# Main.net
KiCad netlist of a schematic drawn in Altium Designer
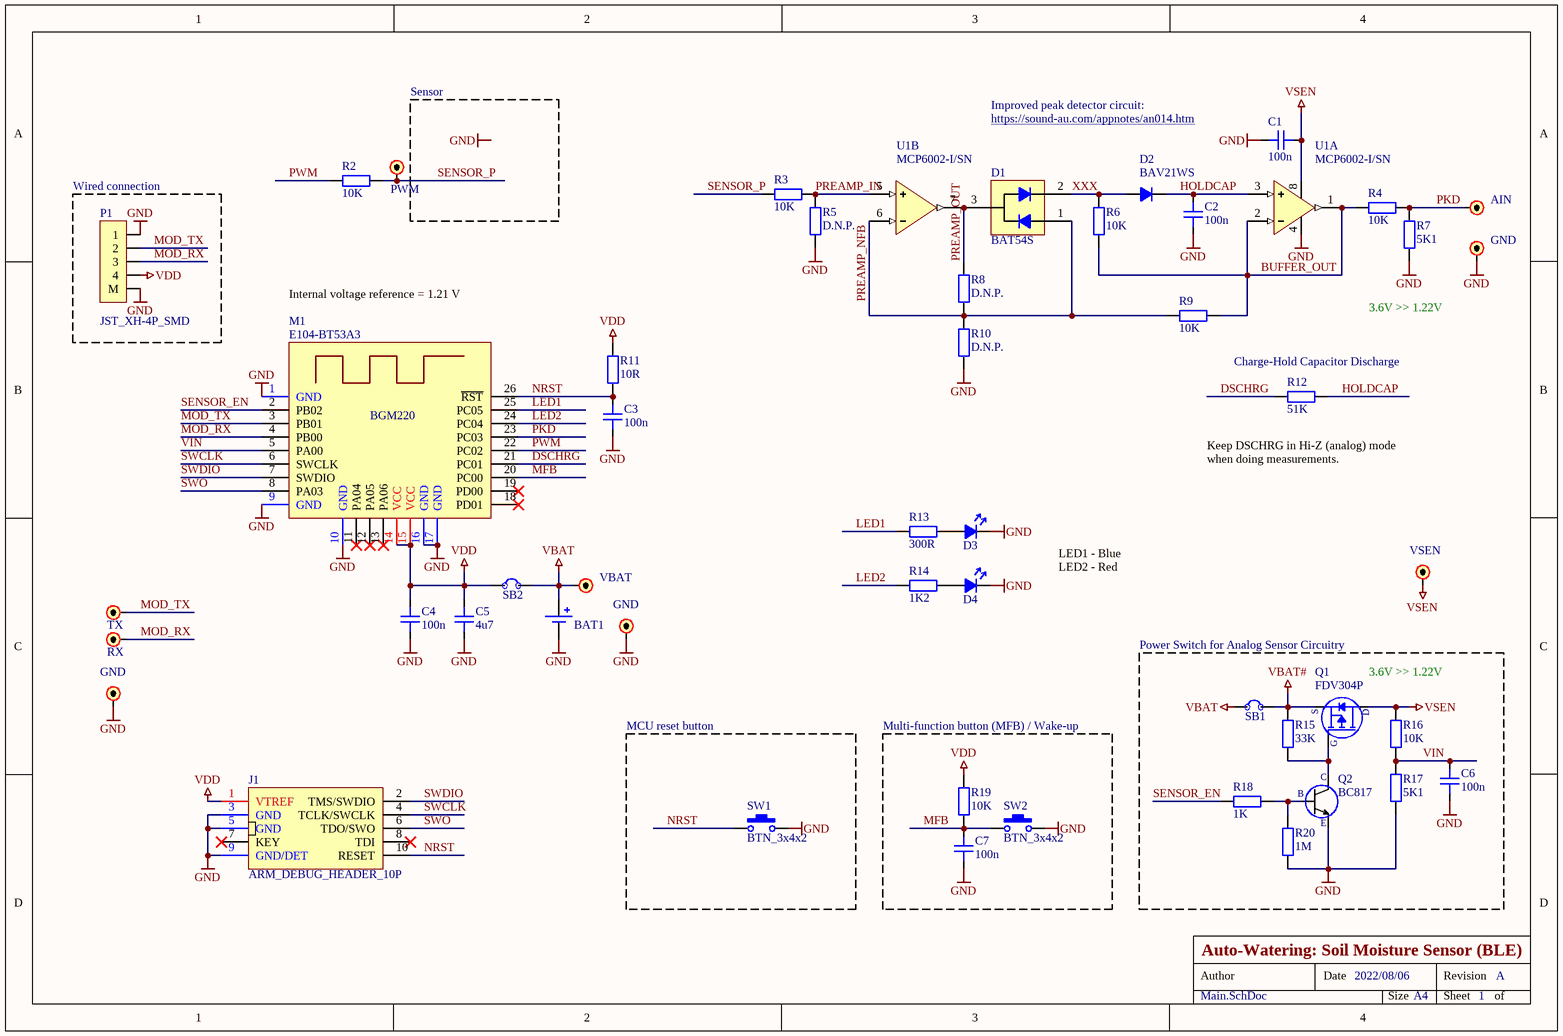
[diagram p0: Main.SchDoc]

(export (version "E")
  (design (tool "Eeschema 10.0.6"))
  (components
    (comp (ref "BAT1")
      (value "WURTH_79527141")
      (footprint "AG.Electromechanical:WURTH_79527141_NO_T-SILK")
      (description "BATT HOLDER COIN 20MM 1 CELL SMD")
      (fields
        (field (name "MANUFACTURER PART NO") "79527141")
        (field (name "MANUFACTURER") "Wurth Electronik")
      )
      (libsource (lib "AG.Holder") (part "WURTH_79527141"))
    )
    (comp (ref "C1")
      (value "100n")
      (footprint "0603C_RF_M")
      (description "Capacitor")
      (fields (field (name "TOLERANCE") "?") (field (name "MANUFACTURER") "Generic Brand"))
      (libsource (lib "AG.Generic") (part "C"))
    )
    (comp (ref "C2")
      (value "100n")
      (footprint "0603C_RF_M")
      (description "Capacitor")
      (fields (field (name "TOLERANCE") "?") (field (name "MANUFACTURER") "Generic Brand"))
      (libsource (lib "AG.Generic") (part "C"))
    )
    (comp (ref "C3")
      (value "100n")
      (footprint "0603C_RF_M")
      (description "Capacitor")
      (fields (field (name "TOLERANCE") "?") (field (name "MANUFACTURER") "Generic Brand"))
      (libsource (lib "AG.Generic") (part "C"))
    )
    (comp (ref "C4")
      (value "100n")
      (footprint "0603C_RF_M")
      (description "Capacitor")
      (fields (field (name "TOLERANCE") "?") (field (name "MANUFACTURER") "Generic Brand"))
      (libsource (lib "AG.Generic") (part "C"))
    )
    (comp (ref "C5")
      (value "4u7")
      (footprint "0603C_RF_M")
      (description "Capacitor")
      (fields (field (name "TOLERANCE") "?") (field (name "MANUFACTURER") "Generic Brand"))
      (libsource (lib "AG.Generic") (part "C"))
    )
    (comp (ref "C6")
      (value "100n")
      (footprint "0603C_RF_M")
      (description "Capacitor")
      (fields (field (name "TOLERANCE") "?") (field (name "MANUFACTURER") "Generic Brand"))
      (libsource (lib "AG.Generic") (part "C"))
    )
    (comp (ref "C7")
      (value "100n")
      (footprint "0603C_RF_M")
      (description "Capacitor")
      (fields (field (name "TOLERANCE") "?") (field (name "MANUFACTURER") "Generic Brand"))
      (libsource (lib "AG.Generic") (part "C"))
    )
    (comp (ref "D1")
      (value "BAT54S")
      (footprint "IRLML_SOT-23")
      (description "DIODE ARRAY SCHOTTKY SERIES 30V 0.2A SOT-23")
      (fields (field (name "MANUFACTURER") "Diodes Incorporated"))
      (libsource (lib "AG.Discrete") (part "BAT54S"))
    )
    (comp (ref "D2")
      (value "BAV21WS")
      (footprint "Generic:D_SOD-323")
      (description "DIODE GEN PURP 200V 200MA SOD323")
      (fields (field (name "MANUFACTURER") "Diotec"))
      (libsource (lib "Diode") (part "BAV21WS"))
    )
    (comp (ref "D3")
      (value "Unspecified")
      (footprint "0805LED_RF_M")
      (description "LED")
      (fields (field (name "MANUFACTURER") "Generic Brand"))
      (libsource (lib "AG.Generic") (part "LED"))
    )
    (comp (ref "D4")
      (value "Unspecified")
      (footprint "0805LED_RF_M")
      (description "LED")
      (fields (field (name "MANUFACTURER") "Generic Brand"))
      (libsource (lib "AG.Generic") (part "LED"))
    )
    (comp (ref "J1")
      (value "ARM_DEBUG_HEADER_10P")
      (footprint "AG.Connectors:ARM_CORTEX_DEBUG_HEADER-1.27-10P-2R_NOMASK")
      (description "ARM Cortex Debug 10-Pin Header")
      (libsource (lib "AG.Connectors") (part "ARM_DEBUG_HEADER_10P"))
    )
    (comp (ref "M1")
      (value "E104-BT53A3")
      (footprint "AG.Modules:E104-BT53A3")
      (description "RXTX MOD BLUETOOTH SOC EFR32BG22C224F512GM32")
      (libsource (lib "AG.Modules") (part "E104-BT53A3"))
    )
    (comp (ref "P1")
      (value "JST_XH-4P_SMD")
      (footprint "AG.Connectors:S4BXHSM4TBLFSN")
      (libsource (lib "AG.Connectors") (part "JST_XH-4P_SMD"))
    )
    (comp (ref "Q1")
      (value "FDV304P")
      (footprint "IRLML_SOT-23")
      (description "MOSFET P-CH 25V 460MA SOT23")
      (fields (field (name "MANUFACTURER") "ON Semiconductor (Fairchild)"))
      (libsource (lib "Transistor") (part "FDV304P"))
    )
    (comp (ref "Q2")
      (value "BC817")
      (footprint "IRLML_SOT-23")
      (description "TRANS NPN 45V 0.5A SOT23")
      (fields
        (field (name "MANUFACTURER") "Nexperia USA Inc.")
        (field (name "MANUFACTURER PART NO") "BC817-40,215")
      )
      (libsource (lib "Transistor") (part "BC817-40-215"))
    )
    (comp (ref "R2")
      (value "10K")
      (footprint "0603R_RF_M")
      (description "Resistor")
      (fields (field (name "TOLERANCE") "?") (field (name "MANUFACTURER") "Generic Brand"))
      (libsource (lib "AG.Generic") (part "R"))
    )
    (comp (ref "R3")
      (value "10K")
      (footprint "0603R_RF_M")
      (description "Resistor")
      (fields (field (name "TOLERANCE") "?") (field (name "MANUFACTURER") "Generic Brand"))
      (libsource (lib "AG.Generic") (part "R"))
    )
    (comp (ref "R4")
      (value "10K")
      (footprint "0603R_RF_M")
      (description "Resistor")
      (fields (field (name "TOLERANCE") "?") (field (name "MANUFACTURER") "Generic Brand"))
      (libsource (lib "AG.Generic") (part "R"))
    )
    (comp (ref "R5")
      (value "D.N.P.")
      (footprint "0603R_RF_M")
      (description "Resistor")
      (fields (field (name "TOLERANCE") "?") (field (name "MANUFACTURER") "Generic Brand"))
      (libsource (lib "AG.Generic") (part "R"))
    )
    (comp (ref "R6")
      (value "10K")
      (footprint "0603R_RF_M")
      (description "Resistor")
      (fields (field (name "TOLERANCE") "?") (field (name "MANUFACTURER") "Generic Brand"))
      (libsource (lib "AG.Generic") (part "R"))
    )
    (comp (ref "R7")
      (value "5K1")
      (footprint "0603R_RF_M")
      (description "Resistor")
      (fields (field (name "TOLERANCE") "?") (field (name "MANUFACTURER") "Generic Brand"))
      (libsource (lib "AG.Generic") (part "R"))
    )
    (comp (ref "R8")
      (value "D.N.P.")
      (footprint "0603R_RF_M")
      (description "Resistor")
      (fields (field (name "TOLERANCE") "?") (field (name "MANUFACTURER") "Generic Brand"))
      (libsource (lib "AG.Generic") (part "R"))
    )
    (comp (ref "R9")
      (value "10K")
      (footprint "0603R_RF_M")
      (description "Resistor")
      (fields (field (name "TOLERANCE") "?") (field (name "MANUFACTURER") "Generic Brand"))
      (libsource (lib "AG.Generic") (part "R"))
    )
    (comp (ref "R10")
      (value "D.N.P.")
      (footprint "0603R_RF_M")
      (description "Resistor")
      (fields (field (name "TOLERANCE") "?") (field (name "MANUFACTURER") "Generic Brand"))
      (libsource (lib "AG.Generic") (part "R"))
    )
    (comp (ref "R11")
      (value "10R")
      (footprint "0603R_RF_M")
      (description "Resistor")
      (fields (field (name "TOLERANCE") "?") (field (name "MANUFACTURER") "Generic Brand"))
      (libsource (lib "AG.Generic") (part "R"))
    )
    (comp (ref "R12")
      (value "51K")
      (footprint "0603R_RF_M")
      (description "Resistor")
      (fields (field (name "TOLERANCE") "?") (field (name "MANUFACTURER") "Generic Brand"))
      (libsource (lib "AG.Generic") (part "R"))
    )
    (comp (ref "R13")
      (value "300R")
      (footprint "0603R_RF_M")
      (description "Resistor")
      (fields (field (name "TOLERANCE") "?") (field (name "MANUFACTURER") "Generic Brand"))
      (libsource (lib "AG.Generic") (part "R"))
    )
    (comp (ref "R14")
      (value "1K2")
      (footprint "0603R_RF_M")
      (description "Resistor")
      (fields (field (name "TOLERANCE") "?") (field (name "MANUFACTURER") "Generic Brand"))
      (libsource (lib "AG.Generic") (part "R"))
    )
    (comp (ref "R15")
      (value "33K")
      (footprint "0603R_RF_M")
      (description "Resistor")
      (fields (field (name "TOLERANCE") "?") (field (name "MANUFACTURER") "Generic Brand"))
      (libsource (lib "AG.Generic") (part "R"))
    )
    (comp (ref "R16")
      (value "10K")
      (footprint "0603R_RF_M")
      (description "Resistor")
      (fields (field (name "TOLERANCE") "?") (field (name "MANUFACTURER") "Generic Brand"))
      (libsource (lib "AG.Generic") (part "R"))
    )
    (comp (ref "R17")
      (value "5K1")
      (footprint "0603R_RF_M")
      (description "Resistor")
      (fields (field (name "TOLERANCE") "?") (field (name "MANUFACTURER") "Generic Brand"))
      (libsource (lib "AG.Generic") (part "R"))
    )
    (comp (ref "R18")
      (value "1K")
      (footprint "0603R_RF_M")
      (description "Resistor")
      (fields (field (name "TOLERANCE") "?") (field (name "MANUFACTURER") "Generic Brand"))
      (libsource (lib "AG.Generic") (part "R"))
    )
    (comp (ref "R19")
      (value "10K")
      (footprint "0603R_RF_M")
      (description "Resistor")
      (fields (field (name "TOLERANCE") "?") (field (name "MANUFACTURER") "Generic Brand"))
      (libsource (lib "AG.Generic") (part "R"))
    )
    (comp (ref "R20")
      (value "1M")
      (footprint "0603R_RF_M")
      (description "Resistor")
      (fields (field (name "TOLERANCE") "?") (field (name "MANUFACTURER") "Generic Brand"))
      (libsource (lib "AG.Generic") (part "R"))
    )
    (comp (ref "SB1")
      (value "Solder Bridge")
      (footprint "AG.Misc:SLDR_BRDG_0603_OPEN")
      (libsource (lib "AG.Misc") (part "Solder Bridge"))
    )
    (comp (ref "SB2")
      (value "Solder Bridge")
      (footprint "AG.Misc:SLDR_BRDG_0603_OPEN")
      (libsource (lib "AG.Misc") (part "Solder Bridge"))
    )
    (comp (ref "SW1")
      (value "BTN_3x4x2")
      (footprint "AG.Electromechanical:BTN_3x4x2")
      (description "Switch Micro SMD 3x4x2 mm Unbranded")
      (libsource (lib "Button") (part "BTN_3x4x2"))
    )
    (comp (ref "SW2")
      (value "BTN_3x4x2")
      (footprint "AG.Electromechanical:BTN_3x4x2")
      (description "Switch Micro SMD 3x4x2 mm Unbranded")
      (libsource (lib "Button") (part "BTN_3x4x2"))
    )
    (comp (ref "TP1")
      (value "PWM")
      (footprint "PAD_R_1MM")
      (description "Test Point / Pad")
      (libsource (lib "AG.Misc") (part "Test Point"))
    )
    (comp (ref "TP2")
      (value "VSEN")
      (footprint "PAD_R_1MM")
      (description "Test Point / Pad")
      (libsource (lib "AG.Misc") (part "Test Point"))
    )
    (comp (ref "TP4")
      (value "AIN")
      (footprint "PAD_R_1MM")
      (description "Test Point / Pad")
      (libsource (lib "AG.Misc") (part "Test Point"))
    )
    (comp (ref "TP5")
      (value "GND")
      (footprint "PAD_R_1MM")
      (description "Test Point / Pad")
      (libsource (lib "AG.Misc") (part "Test Point"))
    )
    (comp (ref "TP6")
      (value "VBAT")
      (footprint "PAD_R_1MM")
      (description "Test Point / Pad")
      (libsource (lib "AG.Misc") (part "Test Point"))
    )
    (comp (ref "TP7")
      (value "TX")
      (footprint "PAD_R_1MM")
      (description "Test Point / Pad")
      (libsource (lib "AG.Misc") (part "Test Point"))
    )
    (comp (ref "TP8")
      (value "GND")
      (footprint "PAD_R_1MM")
      (description "Test Point / Pad")
      (libsource (lib "AG.Misc") (part "Test Point"))
    )
    (comp (ref "TP9")
      (value "RX")
      (footprint "PAD_R_1MM")
      (description "Test Point / Pad")
      (libsource (lib "AG.Misc") (part "Test Point"))
    )
    (comp (ref "TP10")
      (value "GND")
      (footprint "PAD_R_1MM")
      (description "Test Point / Pad")
      (libsource (lib "AG.Misc") (part "Test Point"))
    )
    (comp (ref "U1")
      (value "MCP6002-I/SN")
      (footprint "Generic:SOIC-8")
      (description "IC OPAMP GP 2 CIRCUIT 8SOIC")
      (libsource (lib "AG.IC") (part "MCP6002-I/SN"))
    )
  )
  (nets
    (net (code "1") (name "/BUFFER_OUT") (class "Default")
      (node (ref "R4") (pin "1") (pintype "passive"))
      (node (ref "R6") (pin "2") (pintype "passive"))
      (node (ref "R9") (pin "2") (pintype "passive"))
      (node (ref "U1") (pin "1") (pintype "output"))
      (node (ref "U1") (pin "2") (pintype "input"))
    )
    (net (code "2") (name "/DSCHRG") (class "Default")
      (node (ref "M1") (pin "21") (pinfunction "PC01_21") (pintype "passive"))
      (node (ref "R12") (pin "1") (pintype "passive"))
    )
    (net (code "3") (name "/HOLDCAP") (class "Default")
      (node (ref "C2") (pin "1") (pinfunction "1_1") (pintype "passive"))
      (node (ref "D2") (pin "C") (pinfunction "C_C") (pintype "passive"))
      (node (ref "R12") (pin "2") (pintype "passive"))
      (node (ref "U1") (pin "3") (pintype "input"))
    )
    (net (code "4") (name "/LED1") (class "Default")
      (node (ref "M1") (pin "25") (pinfunction "PC05_25") (pintype "passive"))
      (node (ref "R13") (pin "1") (pintype "passive"))
    )
    (net (code "5") (name "/LED2") (class "Default")
      (node (ref "M1") (pin "24") (pinfunction "PC04_24") (pintype "passive"))
      (node (ref "R14") (pin "1") (pintype "passive"))
    )
    (net (code "6") (name "/MFB") (class "Default")
      (node (ref "C7") (pin "2") (pinfunction "2_2") (pintype "passive"))
      (node (ref "M1") (pin "20") (pinfunction "PC00_20") (pintype "passive"))
      (node (ref "R19") (pin "1") (pintype "passive"))
      (node (ref "SW2") (pin "1") (pinfunction "1_1") (pintype "passive"))
    )
    (net (code "7") (name "/MOD_RX") (class "Default")
      (node (ref "M1") (pin "4") (pinfunction "PB00_4") (pintype "passive"))
      (node (ref "P1") (pin "3") (pinfunction "3_3") (pintype "passive"))
      (node (ref "TP9") (pin "1") (pinfunction "1_1") (pintype "passive"))
    )
    (net (code "8") (name "/MOD_TX") (class "Default")
      (node (ref "M1") (pin "3") (pinfunction "PB01_3") (pintype "passive"))
      (node (ref "P1") (pin "2") (pinfunction "2_2") (pintype "passive"))
      (node (ref "TP7") (pin "1") (pinfunction "1_1") (pintype "passive"))
    )
    (net (code "9") (name "/NRST") (class "Default")
      (node (ref "C3") (pin "2") (pinfunction "2_2") (pintype "passive"))
      (node (ref "J1") (pin "10") (pinfunction "RESET_10") (pintype "passive"))
      (node (ref "M1") (pin "26") (pinfunction "~{RST}_26") (pintype "passive"))
      (node (ref "R11") (pin "1") (pintype "passive"))
      (node (ref "SW1") (pin "1") (pinfunction "1_1") (pintype "passive"))
    )
    (net (code "10") (name "/PKD") (class "Default")
      (node (ref "M1") (pin "23") (pinfunction "PC03_23") (pintype "passive"))
      (node (ref "R4") (pin "2") (pintype "passive"))
      (node (ref "R7") (pin "2") (pintype "passive"))
      (node (ref "TP4") (pin "1") (pinfunction "1_1") (pintype "passive"))
    )
    (net (code "11") (name "/PREAMP_IN") (class "Default")
      (node (ref "R3") (pin "2") (pintype "passive"))
      (node (ref "R5") (pin "2") (pintype "passive"))
      (node (ref "U1") (pin "5") (pintype "input"))
    )
    (net (code "12") (name "/PREAMP_NFB") (class "Default")
      (node (ref "D1") (pin "1") (pinfunction "A1_1") (pintype "passive"))
      (node (ref "R10") (pin "2") (pintype "passive"))
      (node (ref "R8") (pin "1") (pintype "passive"))
      (node (ref "R9") (pin "1") (pintype "passive"))
      (node (ref "U1") (pin "6") (pintype "input"))
    )
    (net (code "13") (name "/PREAMP_OUT") (class "Default")
      (node (ref "D1") (pin "3") (pinfunction "C_3") (pintype "passive"))
      (node (ref "R8") (pin "2") (pintype "passive"))
      (node (ref "U1") (pin "7") (pintype "output"))
    )
    (net (code "14") (name "/PWM") (class "Default")
      (node (ref "M1") (pin "22") (pinfunction "PC02_22") (pintype "passive"))
      (node (ref "R2") (pin "1") (pintype "passive"))
    )
    (net (code "15") (name "/SENSOR_EN") (class "Default")
      (node (ref "M1") (pin "2") (pinfunction "PB02_2") (pintype "passive"))
      (node (ref "R18") (pin "1") (pintype "passive"))
    )
    (net (code "16") (name "/SENSOR_P") (class "Default")
      (node (ref "R2") (pin "2") (pintype "passive"))
      (node (ref "R3") (pin "1") (pintype "passive"))
      (node (ref "TP1") (pin "1") (pinfunction "1_1") (pintype "passive"))
    )
    (net (code "17") (name "/SWCLK") (class "Default")
      (node (ref "J1") (pin "4") (pinfunction "TCLK/SWCLK_4") (pintype "passive"))
      (node (ref "M1") (pin "6") (pinfunction "SWCLK_6") (pintype "passive"))
    )
    (net (code "18") (name "/SWDIO") (class "Default")
      (node (ref "J1") (pin "2") (pinfunction "TMS/SWDIO_2") (pintype "passive"))
      (node (ref "M1") (pin "7") (pinfunction "SWDIO_7") (pintype "passive"))
    )
    (net (code "19") (name "/SWO") (class "Default")
      (node (ref "J1") (pin "6") (pinfunction "TDO/SWO_6") (pintype "passive"))
      (node (ref "M1") (pin "8") (pinfunction "PA03_8") (pintype "passive"))
    )
    (net (code "20") (name "/VIN") (class "Default")
      (node (ref "C6") (pin "1") (pinfunction "1_1") (pintype "passive"))
      (node (ref "M1") (pin "5") (pinfunction "PA00_5") (pintype "passive"))
      (node (ref "R16") (pin "1") (pintype "passive"))
      (node (ref "R17") (pin "2") (pintype "passive"))
    )
    (net (code "21") (name "/XXX") (class "Default")
      (node (ref "D1") (pin "2") (pinfunction "A2_2") (pintype "passive"))
      (node (ref "D2") (pin "A") (pinfunction "A_A") (pintype "passive"))
      (node (ref "R6") (pin "1") (pintype "passive"))
    )
    (net (code "22") (name "GND") (class "Default")
      (node (ref "BAT1") (pin "N") (pinfunction "N_N") (pintype "power_in"))
      (node (ref "C1") (pin "2") (pinfunction "2_2") (pintype "passive"))
      (node (ref "C2") (pin "2") (pinfunction "2_2") (pintype "passive"))
      (node (ref "C3") (pin "1") (pinfunction "1_1") (pintype "passive"))
      (node (ref "C4") (pin "1") (pinfunction "1_1") (pintype "passive"))
      (node (ref "C5") (pin "1") (pinfunction "1_1") (pintype "passive"))
      (node (ref "C6") (pin "2") (pinfunction "2_2") (pintype "passive"))
      (node (ref "C7") (pin "1") (pinfunction "1_1") (pintype "passive"))
      (node (ref "D3") (pin "C") (pinfunction "C_C") (pintype "passive"))
      (node (ref "D4") (pin "C") (pinfunction "C_C") (pintype "passive"))
      (node (ref "J1") (pin "3") (pinfunction "GND_3") (pintype "passive"))
      (node (ref "J1") (pin "5") (pinfunction "GND_5") (pintype "passive"))
      (node (ref "J1") (pin "9") (pinfunction "GND/DET_9") (pintype "passive"))
      (node (ref "M1") (pin "1") (pinfunction "GND_1") (pintype "passive"))
      (node (ref "M1") (pin "10") (pinfunction "GND_10") (pintype "passive"))
      (node (ref "M1") (pin "16") (pinfunction "GND_16") (pintype "passive"))
      (node (ref "M1") (pin "17") (pinfunction "GND_17") (pintype "passive"))
      (node (ref "M1") (pin "9") (pinfunction "GND_9") (pintype "passive"))
      (node (ref "P1") (pin "1") (pinfunction "1_1") (pintype "passive"))
      (node (ref "P1") (pin "MNT") (pinfunction "M_MNT") (pintype "passive"))
      (node (ref "Q2") (pin "2") (pinfunction "Emmiter_2") (pintype "passive"))
      (node (ref "R10") (pin "1") (pintype "passive"))
      (node (ref "R17") (pin "1") (pintype "passive"))
      (node (ref "R20") (pin "1") (pintype "passive"))
      (node (ref "R5") (pin "1") (pintype "passive"))
      (node (ref "R7") (pin "1") (pintype "passive"))
      (node (ref "SW1") (pin "2") (pinfunction "2_2") (pintype "passive"))
      (node (ref "SW2") (pin "2") (pinfunction "2_2") (pintype "passive"))
      (node (ref "TP10") (pin "1") (pinfunction "1_1") (pintype "passive"))
      (node (ref "TP5") (pin "1") (pinfunction "1_1") (pintype "passive"))
      (node (ref "TP8") (pin "1") (pinfunction "1_1") (pintype "passive"))
      (node (ref "U1") (pin "4") (pintype "power_in"))
    )
    (net (code "23") (name "Net-(D3-PadA)") (class "Default")
      (node (ref "D3") (pin "A") (pinfunction "A_A") (pintype "passive"))
      (node (ref "R13") (pin "2") (pintype "passive"))
    )
    (net (code "24") (name "Net-(D4-PadA)") (class "Default")
      (node (ref "D4") (pin "A") (pinfunction "A_A") (pintype "passive"))
      (node (ref "R14") (pin "2") (pintype "passive"))
    )
    (net (code "25") (name "Net-(Q1-Gate)") (class "Default")
      (node (ref "Q1") (pin "1") (pinfunction "Gate_1") (pintype "passive"))
      (node (ref "Q2") (pin "3") (pinfunction "Collector_3") (pintype "passive"))
      (node (ref "R15") (pin "1") (pintype "passive"))
    )
    (net (code "26") (name "Net-(Q2-Base)") (class "Default")
      (node (ref "Q2") (pin "1") (pinfunction "Base_1") (pintype "passive"))
      (node (ref "R18") (pin "2") (pintype "passive"))
      (node (ref "R20") (pin "2") (pintype "passive"))
    )
    (net (code "27") (name "VBAT") (class "Default")
      (node (ref "BAT1") (pin "P") (pinfunction "P_P") (pintype "power_in"))
      (node (ref "SB1") (pin "1") (pinfunction "1_1") (pintype "passive"))
      (node (ref "SB2") (pin "2") (pinfunction "2_2") (pintype "passive"))
      (node (ref "TP6") (pin "1") (pinfunction "1_1") (pintype "passive"))
    )
    (net (code "28") (name "VBAT#") (class "Default")
      (node (ref "Q1") (pin "2") (pinfunction "Source_2") (pintype "passive"))
      (node (ref "R15") (pin "2") (pintype "passive"))
      (node (ref "SB1") (pin "2") (pinfunction "2_2") (pintype "passive"))
    )
    (net (code "29") (name "VDD") (class "Default")
      (node (ref "C4") (pin "2") (pinfunction "2_2") (pintype "passive"))
      (node (ref "C5") (pin "2") (pinfunction "2_2") (pintype "passive"))
      (node (ref "J1") (pin "1") (pinfunction "VTREF_1") (pintype "passive"))
      (node (ref "M1") (pin "14") (pinfunction "VCC_14") (pintype "passive"))
      (node (ref "M1") (pin "15") (pinfunction "VCC_15") (pintype "passive"))
      (node (ref "P1") (pin "4") (pinfunction "4_4") (pintype "passive"))
      (node (ref "R11") (pin "2") (pintype "passive"))
      (node (ref "R19") (pin "2") (pintype "passive"))
      (node (ref "SB2") (pin "1") (pinfunction "1_1") (pintype "passive"))
    )
    (net (code "30") (name "VSEN") (class "Default")
      (node (ref "C1") (pin "1") (pinfunction "1_1") (pintype "passive"))
      (node (ref "Q1") (pin "3") (pinfunction "Drain_3") (pintype "passive"))
      (node (ref "R16") (pin "2") (pintype "passive"))
      (node (ref "TP2") (pin "1") (pinfunction "1_1") (pintype "passive"))
      (node (ref "U1") (pin "8") (pintype "power_in"))
    )
    (net (code "31") (name "unconnected-(J1-KEY-Pad7)") (class "Default")
      (node (ref "J1") (pin "7") (pinfunction "KEY_7") (pintype "passive+no_connect"))
    )
    (net (code "32") (name "unconnected-(J1-TDI-Pad8)") (class "Default")
      (node (ref "J1") (pin "8") (pinfunction "TDI_8") (pintype "passive+no_connect"))
    )
    (net (code "33") (name "unconnected-(M1-PA04-Pad11)") (class "Default")
      (node (ref "M1") (pin "11") (pinfunction "PA04_11") (pintype "passive+no_connect"))
    )
    (net (code "34") (name "unconnected-(M1-PA05-Pad12)") (class "Default")
      (node (ref "M1") (pin "12") (pinfunction "PA05_12") (pintype "passive+no_connect"))
    )
    (net (code "35") (name "unconnected-(M1-PA06-Pad13)") (class "Default")
      (node (ref "M1") (pin "13") (pinfunction "PA06_13") (pintype "passive+no_connect"))
    )
    (net (code "36") (name "unconnected-(M1-PD00-Pad19)") (class "Default")
      (node (ref "M1") (pin "19") (pinfunction "PD00_19") (pintype "passive+no_connect"))
    )
    (net (code "37") (name "unconnected-(M1-PD01-Pad18)") (class "Default")
      (node (ref "M1") (pin "18") (pinfunction "PD01_18") (pintype "passive+no_connect"))
    )
  )
)
